# Motion_Control_Inputs.net
KiCad netlist of a schematic drawn in Altium Designer
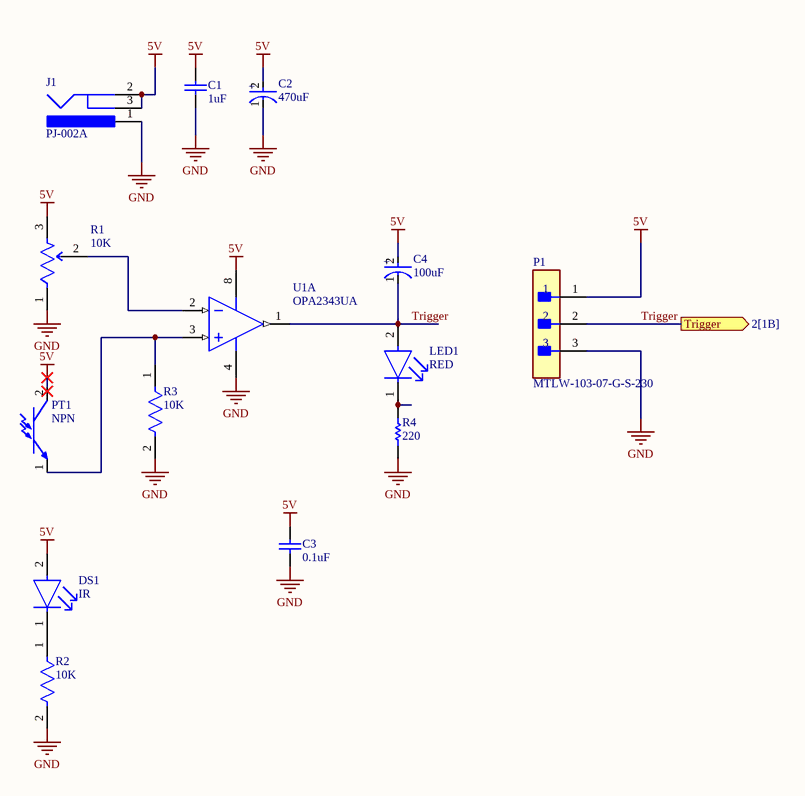
[diagram p0: Motion_Control_Inputs.SchDoc]

(export (version "E")
  (design (tool "Eeschema 10.0.6"))
  (components
    (comp (ref "C1")
      (value "1uF")
      (footprint "CAPC2013X100X50ML20T25")
      (fields (field (name "PART NUMBER") "C0805X105K8RACTU") (field (name "MANUFACTURER") "Kemet"))
      (libsource (lib "MDL") (part "CAP 1uF 10V 0805"))
    )
    (comp (ref "C2")
      (value "470uF")
      (footprint "FP-TR3E-MFG")
      (fields (field (name "VOLTAGE") "10V") (field (name "TOLERANCE") "10%"))
      (libsource (lib "MDL") (part "CAP Pol 470uF 10V SMD"))
    )
    (comp (ref "C3")
      (value "0.1uF")
      (footprint "CAPC2013X145X50ML20T20")
      (fields (field (name "MANUFACTURER") "Vitramon") (field (name "PART NUMBER") "VJ0805Y104MXQCW1BC"))
      (libsource (lib "MDL") (part "CAP 0.1uF 10V 0805"))
    )
    (comp (ref "C4")
      (value "100uF")
      (footprint "FP-TR3B-MFG")
      (fields (field (name "TOLERANCE") "20%"))
      (libsource (lib "MDL") (part "CAP Pol 100uF 10V SMT"))
    )
    (comp (ref "DS1")
      (value "IR")
      (footprint "FP-SFH_4554-MFG")
      (description "EMITTER IR 850NM")
      (fields
        (field (name "MANUFACTURER PART NUMBER") "SFH 4554")
        (field (name "OCTOPART") "https://octopart.com/sfh+4554-osram+opto-55819455")
      )
      (libsource (lib "MDL") (part "IR Emitter 5mm"))
    )
    (comp (ref "J1")
      (value "PJ-002A")
      (footprint "CUI-PJ-002A_V")
      (fields (field (name "MANUFACTURER") "CUIInc."))
      (libsource (lib "MDL") (part "Connector DC Power Jack 2mm"))
    )
    (comp (ref "LED1")
      (value "RED")
      (footprint "FP-HLMP-4700-MFG")
      (description "LED RED DIFFUSED T-1 3/4 T/H")
      (fields
        (field (name "OCTOPART") "https://octopart.com/hlmp-4700-broadcom-71130526")
        (field (name "MANUFACTURER") "Broadcom")
      )
      (libsource (lib "MDL") (part "LED 5mm Red"))
    )
    (comp (ref "P1")
      (value "MTLW-103-07-G-S-230")
      (footprint "FP-MTLW-103-07-G-S-230-MFG")
      (description "CONN HEADER VERT 3POS 2.54MM")
      (libsource (lib "MDL") (part "Header 3POS 2.54mm TH Single Row"))
    )
    (comp (ref "PT1")
      (value "NPN")
      (footprint "PhotoTr_PT334-6C")
      (description "Phototransistor Chip Silicon 940nm 2-Pin T-1 Bag / 5mm Phototransistor, T-1 3/4")
      (fields (field (name "MANUFACTURER") "Everlight") (field (name "MANUFACTURER PART NUMBER") "PT334-6B"))
      (libsource (lib "MDL") (part "Phototransistor 5mm"))
    )
    (comp (ref "R1")
      (value "10K")
      (footprint "FP-TS53YL-MFG")
      (description "TRIMMER 10K OHM 0.25W GW TOP ADJ")
      (fields (field (name "TOLERANCE") "20%"))
      (libsource (lib "MDL") (part "Res 10K Trimmer"))
    )
    (comp (ref "R2")
      (value "10K")
      (footprint "FP-RP73P-2A-IPC_B")
      (description "RP73P 0805 10KΩ 0.25W 25ppm/°C 0.10% 150V")
      (fields
        (field (name "MANUFACTURER PART NUMBER") "RP73PF2A10KBTDF")
        (field (name "MANUFACTURER") "TE Connectivity")
      )
      (libsource (lib "MDL") (part "Res 10K 0.25W SMD"))
    )
    (comp (ref "R3")
      (value "10K")
      (footprint "FP-RP73P-2A-IPC_B")
      (description "RP73P 0805 10KΩ 0.25W 25ppm/°C 0.10% 150V")
      (fields
        (field (name "MANUFACTURER PART NUMBER") "RP73PF2A10KBTDF")
        (field (name "MANUFACTURER") "TE Connectivity")
      )
      (libsource (lib "MDL") (part "Res 10K 0.25W SMD"))
    )
    (comp (ref "R4")
      (value "220")
      (footprint "RESC2013X60X30NL20T20")
      (fields (field (name "PART NUMBER") "SG73S2ATTD2200F") (field (name "MANUFACTURER") "KOA Speer"))
      (libsource (lib "MDL") (part "Res 220 Ohm 0.25W SMD"))
    )
    (comp (ref "U1")
      (value "OPA2343UA")
      (footprint "D0008A_N")
      (fields (field (name "MANUFACTURER") "Texas Instruments"))
      (libsource (lib "MDL") (part "IC OpAmp General Purpose Dual Circuit"))
    )
  )
  (nets
    (net (code "1") (name "/Trigger") (class "Default")
      (node (ref "C4") (pin "1") (pinfunction "C_1") (pintype "passive"))
      (node (ref "LED1") (pin "2") (pinfunction "A_2") (pintype "passive"))
      (node (ref "P1") (pin "2") (pinfunction "2_2") (pintype "passive"))
      (node (ref "U1") (pin "1") (pinfunction "OUT_A_1") (pintype "output"))
    )
    (net (code "2") (name "5V") (class "Default")
      (node (ref "C1") (pin "2") (pinfunction "2_2") (pintype "passive"))
      (node (ref "C2") (pin "2") (pinfunction "A_2") (pintype "passive"))
      (node (ref "C3") (pin "2") (pinfunction "2_2") (pintype "passive"))
      (node (ref "C4") (pin "2") (pinfunction "A_2") (pintype "passive"))
      (node (ref "DS1") (pin "2") (pinfunction "A_2") (pintype "passive"))
      (node (ref "J1") (pin "2") (pinfunction "2_2") (pintype "passive"))
      (node (ref "J1") (pin "3") (pinfunction "3_3") (pintype "passive"))
      (node (ref "P1") (pin "1") (pinfunction "1_1") (pintype "passive"))
      (node (ref "PT1") (pin "2") (pinfunction "C_2") (pintype "open_collector"))
      (node (ref "R1") (pin "3") (pinfunction "c_3") (pintype "passive"))
      (node (ref "U1") (pin "8") (pinfunction "V+_8") (pintype "power_in"))
    )
    (net (code "3") (name "GND") (class "Default")
      (node (ref "C1") (pin "1") (pinfunction "1_1") (pintype "passive"))
      (node (ref "C2") (pin "1") (pinfunction "C_1") (pintype "passive"))
      (node (ref "C3") (pin "1") (pinfunction "1_1") (pintype "passive"))
      (node (ref "J1") (pin "1") (pinfunction "1_1") (pintype "passive"))
      (node (ref "P1") (pin "3") (pinfunction "3_3") (pintype "passive"))
      (node (ref "R1") (pin "1") (pinfunction "a_1") (pintype "passive"))
      (node (ref "R2") (pin "2") (pinfunction "2_2") (pintype "passive"))
      (node (ref "R3") (pin "2") (pinfunction "2_2") (pintype "passive"))
      (node (ref "R4") (pin "2") (pinfunction "2_2") (pintype "passive"))
      (node (ref "U1") (pin "4") (pinfunction "V-_4") (pintype "power_in"))
    )
    (net (code "4") (name "Net-(DS1-C)") (class "Default")
      (node (ref "DS1") (pin "1") (pinfunction "C_1") (pintype "passive"))
      (node (ref "R2") (pin "1") (pinfunction "1_1") (pintype "passive"))
    )
    (net (code "5") (name "Net-(LED1-C)") (class "Default")
      (node (ref "LED1") (pin "1") (pinfunction "C_1") (pintype "passive"))
      (node (ref "R4") (pin "1") (pinfunction "1_1") (pintype "passive"))
    )
    (net (code "6") (name "Net-(PT1-E)") (class "Default")
      (node (ref "PT1") (pin "1") (pinfunction "E_1") (pintype "open_emitter"))
      (node (ref "R3") (pin "1") (pinfunction "1_1") (pintype "passive"))
      (node (ref "U1") (pin "3") (pinfunction "IN_A+_3") (pintype "input"))
    )
    (net (code "7") (name "Net-(R1-b)") (class "Default")
      (node (ref "R1") (pin "2") (pinfunction "b_2") (pintype "passive"))
      (node (ref "U1") (pin "2") (pinfunction "IN_A-_2") (pintype "input"))
    )
  )
)
